# PERIPHERAL.net
KiCad netlist of a schematic drawn in Altium Designer
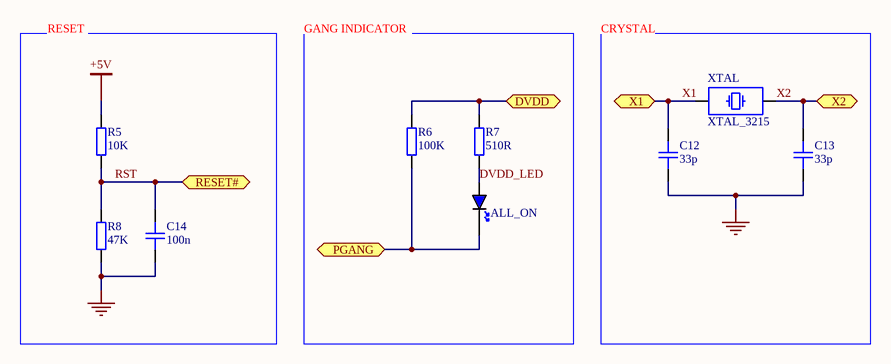
[diagram p0: PERIPHERAL.SchDoc]

(export (version "E")
  (design (tool "Eeschema 10.0.6"))
  (components
    (comp (ref "ALL_ON")
      (value "BLUE")
      (footprint "LED_0603_BLUE")
      (description "LED 0603 BLUE SMD")
      (libsource (lib "Schematic-Lib-PhilsLab") (part "LED_0603_BLUE"))
    )
    (comp (ref "C12")
      (value "33p")
      (footprint "CAP_0402")
      (description "Capacitor SMD 0402")
      (libsource (lib "Schematic-Lib-PhilsLab") (part "CAP_0402"))
    )
    (comp (ref "C13")
      (value "33p")
      (footprint "CAP_0402")
      (description "Capacitor SMD 0402")
      (libsource (lib "Schematic-Lib-PhilsLab") (part "CAP_0402"))
    )
    (comp (ref "C14")
      (value "100n")
      (footprint "CAP_0805")
      (description "Capacitor SMD 0805")
      (libsource (lib "Schematic-Lib-PhilsLab") (part "CAP_0805"))
    )
    (comp (ref "R5")
      (value "10K")
      (footprint "RES_0805")
      (description "Resistor SMD 0805")
      (libsource (lib "Schematic-Lib-PhilsLab") (part "RES_0805"))
    )
    (comp (ref "R6")
      (value "100K")
      (footprint "RES_0603")
      (description "Resistor SMD 0603")
      (libsource (lib "Schematic-Lib-PhilsLab") (part "RES_0603"))
    )
    (comp (ref "R7")
      (value "510R")
      (footprint "RES_0603")
      (description "Resistor SMD 0603")
      (libsource (lib "Schematic-Lib-PhilsLab") (part "RES_0603"))
    )
    (comp (ref "R8")
      (value "47K")
      (footprint "RES_0603")
      (description "Resistor SMD 0603")
      (libsource (lib "Schematic-Lib-PhilsLab") (part "RES_0603"))
    )
    (comp (ref "XTAL")
      (value "XTAL_3215")
      (footprint "XTAL_3215-2")
      (description "Crystal SMD 3215")
      (libsource (lib "Schematic-Lib-PhilsLab") (part "XTAL_3215"))
    )
  )
  (nets
    (net (code "1") (name "+5V") (class "Default")
      (node (ref "R5") (pin "2") (pinfunction "2_2") (pintype "passive"))
    )
    (net (code "2") (name "/DVDD") (class "Default")
      (node (ref "R6") (pin "2") (pinfunction "2_2") (pintype "passive"))
      (node (ref "R7") (pin "2") (pinfunction "2_2") (pintype "passive"))
    )
    (net (code "3") (name "/DVDD_LED") (class "Default")
      (node (ref "ALL_ON") (pin "A") (pinfunction "A_A") (pintype "passive"))
      (node (ref "R7") (pin "1") (pinfunction "1_1") (pintype "passive"))
    )
    (net (code "4") (name "/PGANG") (class "Default")
      (node (ref "ALL_ON") (pin "K") (pinfunction "K_K") (pintype "passive"))
      (node (ref "R6") (pin "1") (pinfunction "1_1") (pintype "passive"))
    )
    (net (code "5") (name "/RST") (class "Default")
      (node (ref "C14") (pin "2") (pinfunction "2_2") (pintype "passive"))
      (node (ref "R5") (pin "1") (pinfunction "1_1") (pintype "passive"))
      (node (ref "R8") (pin "2") (pinfunction "2_2") (pintype "passive"))
    )
    (net (code "6") (name "/X1") (class "Default")
      (node (ref "C12") (pin "2") (pinfunction "2_2") (pintype "passive"))
      (node (ref "XTAL") (pin "1") (pinfunction "1_1") (pintype "passive"))
    )
    (net (code "7") (name "/X2") (class "Default")
      (node (ref "C13") (pin "2") (pinfunction "2_2") (pintype "passive"))
      (node (ref "XTAL") (pin "2") (pinfunction "2_2") (pintype "passive"))
    )
    (net (code "8") (name "GND") (class "Default")
      (node (ref "C12") (pin "1") (pinfunction "1_1") (pintype "passive"))
      (node (ref "C13") (pin "1") (pinfunction "1_1") (pintype "passive"))
      (node (ref "C14") (pin "1") (pinfunction "1_1") (pintype "passive"))
      (node (ref "R8") (pin "1") (pinfunction "1_1") (pintype "passive"))
    )
  )
)
